# stm32H7_experimenter10.net
KiCad netlist of a schematic drawn in EAGLE
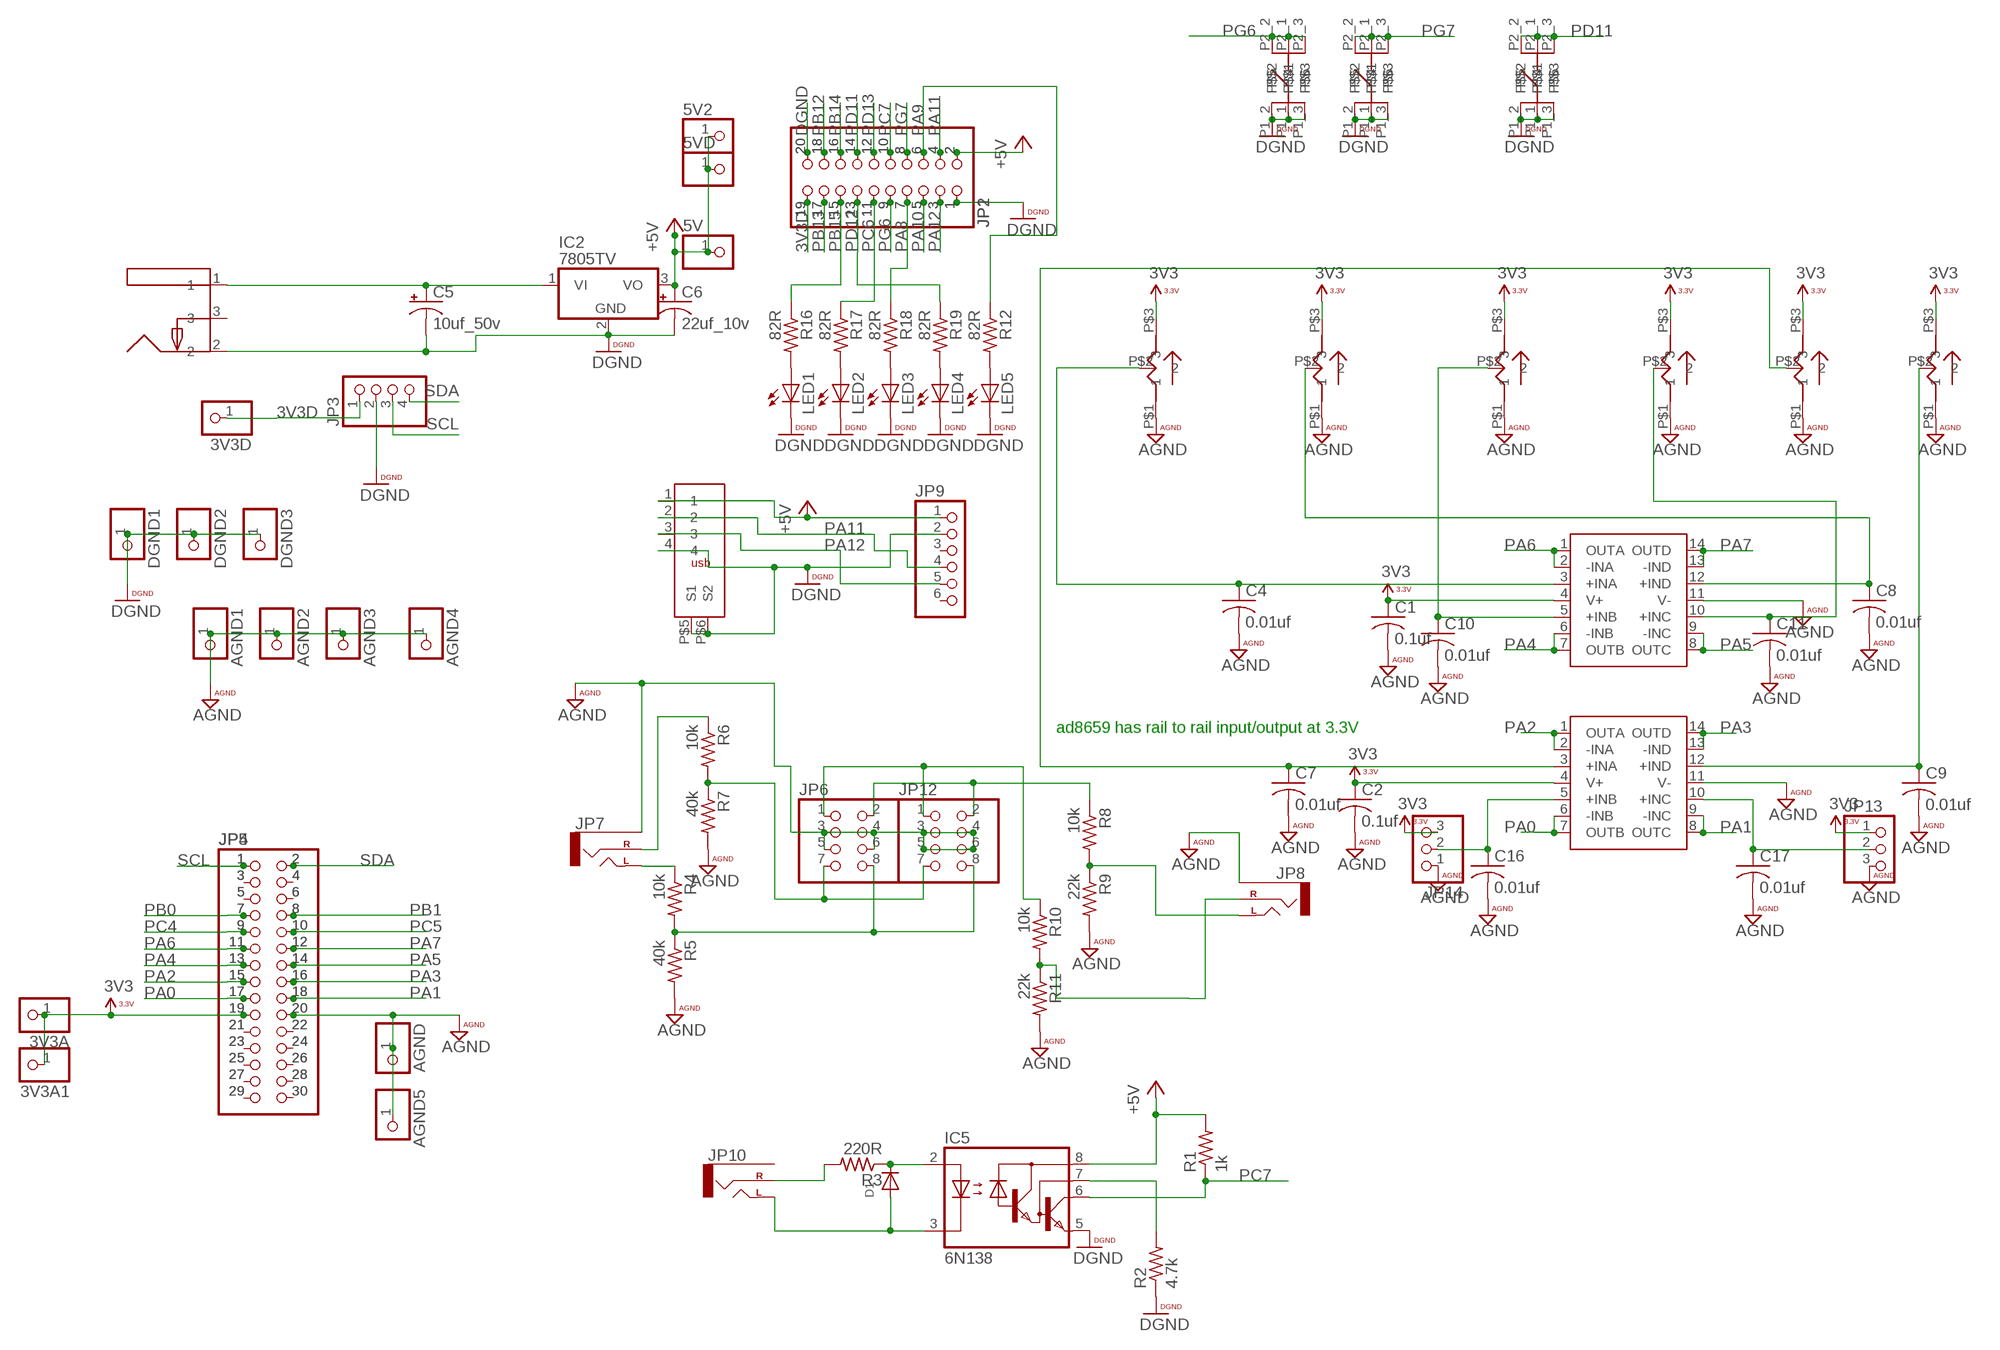
[diagram p0: schematic, sheet 1]

(export (version "E")
  (design (tool "Eeschema 10.0.6"))
  (components
    (comp (ref "3V3A")
      (value "PINHD-1X1")
      (footprint "eagle-import:1X01")
      (fields (field (name "PARTNO") "*DNP"))
      (libsource (lib "eagle-import") (part "PINHD-1X1"))
    )
    (comp (ref "3V3A1")
      (value "PINHD-1X1")
      (footprint "eagle-import:1X01")
      (fields (field (name "PARTNO") "*DNP"))
      (libsource (lib "eagle-import") (part "PINHD-1X1"))
    )
    (comp (ref "3V3D")
      (value "PINHD-1X1")
      (footprint "eagle-import:1X01")
      (fields (field (name "PARTNO") "*DNP"))
      (libsource (lib "eagle-import") (part "PINHD-1X1"))
    )
    (comp (ref "5V")
      (value "PINHD-1X1")
      (footprint "eagle-import:1X01")
      (fields (field (name "PARTNO") "*DNP"))
      (libsource (lib "eagle-import") (part "PINHD-1X1"))
    )
    (comp (ref "5V2")
      (value "PINHD-1X1")
      (footprint "eagle-import:1X01")
      (fields (field (name "PARTNO") "*DNP"))
      (libsource (lib "eagle-import") (part "PINHD-1X1"))
    )
    (comp (ref "5VD")
      (value "PINHD-1X1")
      (footprint "eagle-import:1X01")
      (fields (field (name "PARTNO") "*DNP"))
      (libsource (lib "eagle-import") (part "PINHD-1X1"))
    )
    (comp (ref "AGND")
      (value "PINHD-1X1")
      (footprint "eagle-import:1X01")
      (fields (field (name "PARTNO") "*DNP"))
      (libsource (lib "eagle-import") (part "PINHD-1X1"))
    )
    (comp (ref "AGND1")
      (value "PINHD-1X1")
      (footprint "eagle-import:1X01")
      (fields (field (name "PARTNO") "*DNP"))
      (libsource (lib "eagle-import") (part "PINHD-1X1"))
    )
    (comp (ref "AGND2")
      (value "PINHD-1X1")
      (footprint "eagle-import:1X01")
      (fields (field (name "PARTNO") "*DNP"))
      (libsource (lib "eagle-import") (part "PINHD-1X1"))
    )
    (comp (ref "AGND3")
      (value "PINHD-1X1")
      (footprint "eagle-import:1X01")
      (fields (field (name "PARTNO") "*DNP"))
      (libsource (lib "eagle-import") (part "PINHD-1X1"))
    )
    (comp (ref "AGND4")
      (value "PINHD-1X1")
      (footprint "eagle-import:1X01")
      (fields (field (name "PARTNO") "*DNP"))
      (libsource (lib "eagle-import") (part "PINHD-1X1"))
    )
    (comp (ref "AGND5")
      (value "PINHD-1X1")
      (footprint "eagle-import:1X01")
      (fields (field (name "PARTNO") "*DNP"))
      (libsource (lib "eagle-import") (part "PINHD-1X1"))
    )
    (comp (ref "C1")
      (value "0.1uf")
      (footprint "eagle-import:C025-030X050")
      (fields (field (name "PARTNO") "K104K15X7RF5TL2"))
      (libsource (lib "eagle-import") (part "C-US025-030X050"))
    )
    (comp (ref "C2")
      (value "0.1uf")
      (footprint "eagle-import:C025-030X050")
      (fields (field (name "PARTNO") "K104K15X7RF5TL2"))
      (libsource (lib "eagle-import") (part "C-US025-030X050"))
    )
    (comp (ref "C4")
      (value "0.01uf")
      (footprint "eagle-import:C025-030X050")
      (fields (field (name "PARTNO") "K103K15X7RF5TL2"))
      (libsource (lib "eagle-import") (part "C-US025-030X050"))
    )
    (comp (ref "C5")
      (value "10uf_50v")
      (footprint "eagle-import:SMC_C")
      (fields (field (name "PARTNO") "293D106X9035C2TE3"))
      (libsource (lib "eagle-import") (part "CPOL-USSMCC"))
    )
    (comp (ref "C6")
      (value "22uf_10v")
      (footprint "eagle-import:SMC_C")
      (fields (field (name "PARTNO") "T491C226K016AT"))
      (libsource (lib "eagle-import") (part "CPOL-USSMCC"))
    )
    (comp (ref "C7")
      (value "0.01uf")
      (footprint "eagle-import:C025-030X050")
      (fields (field (name "PARTNO") "K103K15X7RF5TL2"))
      (libsource (lib "eagle-import") (part "C-US025-030X050"))
    )
    (comp (ref "C8")
      (value "0.01uf")
      (footprint "eagle-import:C025-030X050")
      (fields (field (name "PARTNO") "K103K15X7RF5TL2"))
      (libsource (lib "eagle-import") (part "C-US025-030X050"))
    )
    (comp (ref "C9")
      (value "0.01uf")
      (footprint "eagle-import:C025-030X050")
      (fields (field (name "PARTNO") "K103K15X7RF5TL2"))
      (libsource (lib "eagle-import") (part "C-US025-030X050"))
    )
    (comp (ref "C10")
      (value "0.01uf")
      (footprint "eagle-import:C025-030X050")
      (fields (field (name "PARTNO") "K103K15X7RF5TL2"))
      (libsource (lib "eagle-import") (part "C-US025-030X050"))
    )
    (comp (ref "C11")
      (value "0.01uf")
      (footprint "eagle-import:C025-030X050")
      (fields (field (name "PARTNO") "K103K15X7RF5TL2"))
      (libsource (lib "eagle-import") (part "C-US025-030X050"))
    )
    (comp (ref "C16")
      (value "0.01uf")
      (footprint "eagle-import:C025-030X050")
      (fields (field (name "PARTNO") "K103K15X7RF5TL2"))
      (libsource (lib "eagle-import") (part "C-US025-030X050"))
    )
    (comp (ref "C17")
      (value "0.01uf")
      (footprint "eagle-import:C025-030X050")
      (fields (field (name "PARTNO") "K103K15X7RF5TL2"))
      (libsource (lib "eagle-import") (part "C-US025-030X050"))
    )
    (comp (ref "D1")
      (value "DIODEDO-1N4148")
      (footprint "eagle-import:DO-1N4148")
      (fields (field (name "PARTNO") "1N4148"))
      (libsource (lib "eagle-import") (part "DIODEDO-1N4148"))
    )
    (comp (ref "DGND1")
      (value "PINHD-1X1")
      (footprint "eagle-import:1X01")
      (fields (field (name "PARTNO") "*DNP"))
      (libsource (lib "eagle-import") (part "PINHD-1X1"))
    )
    (comp (ref "DGND2")
      (value "PINHD-1X1")
      (footprint "eagle-import:1X01")
      (fields (field (name "PARTNO") "*DNP"))
      (libsource (lib "eagle-import") (part "PINHD-1X1"))
    )
    (comp (ref "DGND3")
      (value "PINHD-1X1")
      (footprint "eagle-import:1X01")
      (fields (field (name "PARTNO") "*DNP"))
      (libsource (lib "eagle-import") (part "PINHD-1X1"))
    )
    (comp (ref "IC1")
      (value "AD8659")
      (footprint "eagle-import:SO14")
      (fields (field (name "PARTNO") "AD8659ARZ-R7"))
      (libsource (lib "eagle-import") (part "AD8659"))
    )
    (comp (ref "IC2")
      (value "7805TV")
      (footprint "eagle-import:TO220V")
      (fields (field (name "PARTNO") "VX7805-1000"))
      (libsource (lib "eagle-import") (part "78TV05"))
    )
    (comp (ref "IC3")
      (value "AD8659")
      (footprint "eagle-import:SO14")
      (fields (field (name "PARTNO") "AD8659ARZ-R7"))
      (libsource (lib "eagle-import") (part "AD8659"))
    )
    (comp (ref "IC5")
      (value "6N138")
      (footprint "eagle-import:DIL08")
      (fields (field (name "MF") "VISHAY/TELEFUNKEN"))
      (libsource (lib "eagle-import") (part "6N138"))
    )
    (comp (ref "JP1")
      (value "PINHD-2X10")
      (footprint "eagle-import:2X10")
      (fields (field (name "PARTNO") "*DNP"))
      (libsource (lib "eagle-import") (part "PINHD-2X10"))
    )
    (comp (ref "JP2")
      (value "PINHD-2X10")
      (footprint "eagle-import:2X10")
      (fields (field (name "PARTNO") "67996-120HLF"))
      (libsource (lib "eagle-import") (part "PINHD-2X10"))
    )
    (comp (ref "JP3")
      (value "PINHD-1X4")
      (footprint "eagle-import:1X04")
      (fields (field (name "PARTNO") "*DNP"))
      (libsource (lib "eagle-import") (part "PINHD-1X4"))
    )
    (comp (ref "JP4")
      (value "PINHD-2X15")
      (footprint "eagle-import:2X15")
      (fields (field (name "PARTNO") "67996-130HLF"))
      (libsource (lib "eagle-import") (part "PINHD-2X15"))
    )
    (comp (ref "JP5")
      (value "PINHD-2X15")
      (footprint "eagle-import:2X15")
      (fields (field (name "PARTNO") "*DNP"))
      (libsource (lib "eagle-import") (part "PINHD-2X15"))
    )
    (comp (ref "JP6")
      (value "PINHD-2X4")
      (footprint "eagle-import:2X04")
      (fields (field (name "PARTNO") "67996-108HLF"))
      (libsource (lib "eagle-import") (part "PINHD-2X4"))
    )
    (comp (ref "JP7")
      (value "AUDIO-JACKPTH")
      (footprint "eagle-import:AUDIO-JACK")
      (fields (field (name "PARTNO") "SJ1-3525N"))
      (libsource (lib "eagle-import") (part "AUDIO-JACKPTH"))
    )
    (comp (ref "JP8")
      (value "AUDIO-JACKPTH")
      (footprint "eagle-import:AUDIO-JACK")
      (fields (field (name "PARTNO") "SJ1-3525N"))
      (libsource (lib "eagle-import") (part "AUDIO-JACKPTH"))
    )
    (comp (ref "JP9")
      (value "PINHD-1X6")
      (footprint "eagle-import:1X06")
      (libsource (lib "eagle-import") (part "PINHD-1X6"))
    )
    (comp (ref "JP10")
      (value "AUDIO-JACKPTH")
      (footprint "eagle-import:AUDIO-JACK")
      (fields (field (name "PARTNO") "SJ1-3525N"))
      (libsource (lib "eagle-import") (part "AUDIO-JACKPTH"))
    )
    (comp (ref "JP12")
      (value "PINHD-2X4")
      (footprint "eagle-import:2X04")
      (fields (field (name "PARTNO") "*DNP"))
      (libsource (lib "eagle-import") (part "PINHD-2X4"))
    )
    (comp (ref "JP13")
      (value "PINHD-1X3")
      (footprint "eagle-import:1X03")
      (fields (field (name "PARTNO") "*DNP"))
      (libsource (lib "eagle-import") (part "PINHD-1X3"))
    )
    (comp (ref "JP14")
      (value "PINHD-1X3")
      (footprint "eagle-import:1X03")
      (fields (field (name "PARTNO") "*DNP"))
      (libsource (lib "eagle-import") (part "PINHD-1X3"))
    )
    (comp (ref "LED1")
      (value "LED3MM")
      (footprint "eagle-import:LED3MM")
      (fields (field (name "PARTNO") "151031SS04000"))
      (libsource (lib "eagle-import") (part "LED3MM"))
    )
    (comp (ref "LED2")
      (value "LED3MM")
      (footprint "eagle-import:LED3MM")
      (fields (field (name "PARTNO") "151031SS04000"))
      (libsource (lib "eagle-import") (part "LED3MM"))
    )
    (comp (ref "LED3")
      (value "LED3MM")
      (footprint "eagle-import:LED3MM")
      (fields (field (name "PARTNO") "151031SS04000"))
      (libsource (lib "eagle-import") (part "LED3MM"))
    )
    (comp (ref "LED4")
      (value "LED3MM")
      (footprint "eagle-import:LED3MM")
      (fields (field (name "PARTNO") "151031SS04000"))
      (libsource (lib "eagle-import") (part "LED3MM"))
    )
    (comp (ref "LED5")
      (value "LED3MM")
      (footprint "eagle-import:LED3MM")
      (fields (field (name "PARTNO") "151031SS04000"))
      (libsource (lib "eagle-import") (part "LED3MM"))
    )
    (comp (ref "P1")
      (value "RK09SONGHUEI")
      (footprint "eagle-import:R0904N")
      (libsource (lib "eagle-import") (part "RK09SONGHUEI"))
    )
    (comp (ref "P2")
      (value "RK09SONGHUEI")
      (footprint "eagle-import:R0904N")
      (libsource (lib "eagle-import") (part "RK09SONGHUEI"))
    )
    (comp (ref "P3")
      (value "RK09SONGHUEI")
      (footprint "eagle-import:R0904N")
      (libsource (lib "eagle-import") (part "RK09SONGHUEI"))
    )
    (comp (ref "P4")
      (value "RK09SONGHUEI")
      (footprint "eagle-import:R0904N")
      (libsource (lib "eagle-import") (part "RK09SONGHUEI"))
    )
    (comp (ref "P5")
      (value "RK09SONGHUEI")
      (footprint "eagle-import:R0904N")
      (libsource (lib "eagle-import") (part "RK09SONGHUEI"))
    )
    (comp (ref "P6")
      (value "RK09SONGHUEI")
      (footprint "eagle-import:R0904N")
      (libsource (lib "eagle-import") (part "RK09SONGHUEI"))
    )
    (comp (ref "R1")
      (value "1k")
      (footprint "eagle-import:0204_5")
      (fields (field (name "PARTNO") "RNMF14FTC1K00"))
      (libsource (lib "eagle-import") (part "R-US_0204/5"))
    )
    (comp (ref "R2")
      (value "4.7k")
      (footprint "eagle-import:0204_5")
      (fields (field (name "PARTNO") "RNMF14FTC4K70"))
      (libsource (lib "eagle-import") (part "R-US_0204/5"))
    )
    (comp (ref "R3")
      (value "220R")
      (footprint "eagle-import:0204_5")
      (fields (field (name "PARTNO") "RNMF14FTC220R"))
      (libsource (lib "eagle-import") (part "R-US_0204/5"))
    )
    (comp (ref "R4")
      (value "10k")
      (footprint "eagle-import:0204_5")
      (fields (field (name "PARTNO") "RNMF14FTC10K0"))
      (libsource (lib "eagle-import") (part "R-US_0204/5"))
    )
    (comp (ref "R5")
      (value "40k")
      (footprint "eagle-import:0204_5")
      (fields (field (name "PARTNO") "RNMF14FTC39K0"))
      (libsource (lib "eagle-import") (part "R-US_0204/5"))
    )
    (comp (ref "R6")
      (value "10k")
      (footprint "eagle-import:0204_5")
      (fields (field (name "PARTNO") "RNMF14FTC10K0"))
      (libsource (lib "eagle-import") (part "R-US_0204/5"))
    )
    (comp (ref "R7")
      (value "40k")
      (footprint "eagle-import:0204_5")
      (fields (field (name "PARTNO") "RNMF14FTC39K0"))
      (libsource (lib "eagle-import") (part "R-US_0204/5"))
    )
    (comp (ref "R8")
      (value "10k")
      (footprint "eagle-import:0204_5")
      (fields (field (name "PARTNO") "RNMF14FTC10K0"))
      (libsource (lib "eagle-import") (part "R-US_0204/5"))
    )
    (comp (ref "R9")
      (value "22k")
      (footprint "eagle-import:0204_5")
      (fields (field (name "PARTNO") "RNMF14FTC22K0"))
      (libsource (lib "eagle-import") (part "R-US_0204/5"))
    )
    (comp (ref "R10")
      (value "10k")
      (footprint "eagle-import:0204_5")
      (fields (field (name "PARTNO") "RNMF14FTC10K0"))
      (libsource (lib "eagle-import") (part "R-US_0204/5"))
    )
    (comp (ref "R11")
      (value "22k")
      (footprint "eagle-import:0204_5")
      (fields (field (name "PARTNO") "RNMF14FTC22K0"))
      (libsource (lib "eagle-import") (part "R-US_0204/5"))
    )
    (comp (ref "R12")
      (value "82R")
      (footprint "eagle-import:0204_5")
      (fields (field (name "PARTNO") "RNMF14FTC82R0"))
      (libsource (lib "eagle-import") (part "R-US_0204/5"))
    )
    (comp (ref "R16")
      (value "82R")
      (footprint "eagle-import:0204V")
      (fields (field (name "PARTNO") "RNMF14FTC82R0"))
      (libsource (lib "eagle-import") (part "R-US_0204/2V"))
    )
    (comp (ref "R17")
      (value "82R")
      (footprint "eagle-import:0204V")
      (fields (field (name "PARTNO") "RNMF14FTC82R0"))
      (libsource (lib "eagle-import") (part "R-US_0204/2V"))
    )
    (comp (ref "R18")
      (value "82R")
      (footprint "eagle-import:0204_5")
      (fields (field (name "PARTNO") "RNMF14FTC82R0"))
      (libsource (lib "eagle-import") (part "R-US_0204/5"))
    )
    (comp (ref "R19")
      (value "82R")
      (footprint "eagle-import:0204_5")
      (fields (field (name "PARTNO") "RNMF14FTC82R0"))
      (libsource (lib "eagle-import") (part "R-US_0204/5"))
    )
    (comp (ref "S1")
      (value "TL52_PLUS")
      (footprint "eagle-import:TL52_PLUS")
      (fields (field (name "PARTNO") "TL52AF160Q"))
      (libsource (lib "eagle-import") (part "TL52_PLUS"))
    )
    (comp (ref "S2")
      (value "TL52_PLUS")
      (footprint "eagle-import:TL52_PLUS")
      (fields (field (name "PARTNO") "TL52AF160Q"))
      (libsource (lib "eagle-import") (part "TL52_PLUS"))
    )
    (comp (ref "S3")
      (value "TL52_PLUS")
      (footprint "eagle-import:TL52_PLUS")
      (fields (field (name "PARTNO") "TL52AF160Q"))
      (libsource (lib "eagle-import") (part "TL52_PLUS"))
    )
    (comp (ref "U$1")
      (value "PJ-058AH_PWR_JACK")
      (footprint "eagle-import:PJ-058AH")
      (libsource (lib "eagle-import") (part "PJ-058AH_PWR_JACK"))
    )
    (comp (ref "U$3")
      (value "USB_292303-1")
      (footprint "eagle-import:292303")
      (libsource (lib "eagle-import") (part "USB_292303-1"))
    )
  )
  (nets
    (net (code "1") (name "+5V") (class "Default")
      (node (ref "5V") (pin "1") (pinfunction "1_1") (pintype "passive"))
      (node (ref "5V2") (pin "1") (pinfunction "1_1") (pintype "passive"))
      (node (ref "5VD") (pin "1") (pinfunction "1_1") (pintype "passive"))
      (node (ref "C6") (pin "+") (pinfunction "+_+") (pintype "passive"))
      (node (ref "IC2") (pin "3") (pinfunction "VO_3") (pintype "passive"))
      (node (ref "IC5") (pin "8") (pinfunction "VCC_8") (pintype "passive"))
      (node (ref "JP1") (pin "2") (pinfunction "2_2") (pintype "passive"))
      (node (ref "JP2") (pin "2") (pinfunction "2_2") (pintype "passive"))
      (node (ref "JP9") (pin "1") (pinfunction "1_1") (pintype "passive"))
      (node (ref "R1") (pin "2") (pinfunction "2_2") (pintype "passive"))
      (node (ref "U$3") (pin "1") (pinfunction "1_1") (pintype "bidirectional"))
    )
    (net (code "2") (name "/3V3D") (class "Default")
      (node (ref "3V3D") (pin "1") (pinfunction "1_1") (pintype "passive"))
      (node (ref "JP1") (pin "19") (pinfunction "19_19") (pintype "passive"))
      (node (ref "JP2") (pin "19") (pinfunction "19_19") (pintype "passive"))
      (node (ref "JP3") (pin "1") (pinfunction "1_1") (pintype "passive"))
    )
    (net (code "3") (name "/PA0") (class "Default")
      (node (ref "IC3") (pin "6") (pinfunction "-INB_6") (pintype "bidirectional"))
      (node (ref "IC3") (pin "7") (pinfunction "OUTB_7") (pintype "bidirectional"))
      (node (ref "JP4") (pin "17") (pinfunction "17_17") (pintype "passive"))
      (node (ref "JP5") (pin "17") (pinfunction "17_17") (pintype "passive"))
    )
    (net (code "4") (name "/PA1") (class "Default")
      (node (ref "IC3") (pin "8") (pinfunction "OUTC_8") (pintype "bidirectional"))
      (node (ref "IC3") (pin "9") (pinfunction "-INC_9") (pintype "bidirectional"))
      (node (ref "JP4") (pin "18") (pinfunction "18_18") (pintype "passive"))
      (node (ref "JP5") (pin "18") (pinfunction "18_18") (pintype "passive"))
    )
    (net (code "5") (name "/PA2") (class "Default")
      (node (ref "IC3") (pin "1") (pinfunction "OUTA_1") (pintype "bidirectional"))
      (node (ref "IC3") (pin "2") (pinfunction "-INA_2") (pintype "bidirectional"))
      (node (ref "JP4") (pin "15") (pinfunction "15_15") (pintype "passive"))
      (node (ref "JP5") (pin "15") (pinfunction "15_15") (pintype "passive"))
    )
    (net (code "6") (name "/PA3") (class "Default")
      (node (ref "IC3") (pin "13") (pinfunction "-IND_13") (pintype "bidirectional"))
      (node (ref "IC3") (pin "14") (pinfunction "OUTD_14") (pintype "bidirectional"))
      (node (ref "JP4") (pin "16") (pinfunction "16_16") (pintype "passive"))
      (node (ref "JP5") (pin "16") (pinfunction "16_16") (pintype "passive"))
    )
    (net (code "7") (name "/PA4") (class "Default")
      (node (ref "IC1") (pin "6") (pinfunction "-INB_6") (pintype "bidirectional"))
      (node (ref "IC1") (pin "7") (pinfunction "OUTB_7") (pintype "bidirectional"))
      (node (ref "JP4") (pin "13") (pinfunction "13_13") (pintype "passive"))
      (node (ref "JP5") (pin "13") (pinfunction "13_13") (pintype "passive"))
    )
    (net (code "8") (name "/PA5") (class "Default")
      (node (ref "IC1") (pin "8") (pinfunction "OUTC_8") (pintype "bidirectional"))
      (node (ref "IC1") (pin "9") (pinfunction "-INC_9") (pintype "bidirectional"))
      (node (ref "JP4") (pin "14") (pinfunction "14_14") (pintype "passive"))
      (node (ref "JP5") (pin "14") (pinfunction "14_14") (pintype "passive"))
    )
    (net (code "9") (name "/PA6") (class "Default")
      (node (ref "IC1") (pin "1") (pinfunction "OUTA_1") (pintype "bidirectional"))
      (node (ref "IC1") (pin "2") (pinfunction "-INA_2") (pintype "bidirectional"))
      (node (ref "JP4") (pin "11") (pinfunction "11_11") (pintype "passive"))
      (node (ref "JP5") (pin "11") (pinfunction "11_11") (pintype "passive"))
    )
    (net (code "10") (name "/PA7") (class "Default")
      (node (ref "IC1") (pin "13") (pinfunction "-IND_13") (pintype "bidirectional"))
      (node (ref "IC1") (pin "14") (pinfunction "OUTD_14") (pintype "bidirectional"))
      (node (ref "JP4") (pin "12") (pinfunction "12_12") (pintype "passive"))
      (node (ref "JP5") (pin "12") (pinfunction "12_12") (pintype "passive"))
    )
    (net (code "11") (name "/PA8") (class "Default")
      (node (ref "JP1") (pin "7") (pinfunction "7_7") (pintype "passive"))
      (node (ref "JP2") (pin "7") (pinfunction "7_7") (pintype "passive"))
      (node (ref "R18") (pin "1") (pinfunction "1_1") (pintype "passive"))
    )
    (net (code "12") (name "/PA9") (class "Default")
      (node (ref "JP1") (pin "6") (pinfunction "6_6") (pintype "passive"))
      (node (ref "JP2") (pin "6") (pinfunction "6_6") (pintype "passive"))
      (node (ref "R12") (pin "1") (pinfunction "1_1") (pintype "passive"))
    )
    (net (code "13") (name "/PA10") (class "Default")
      (node (ref "JP1") (pin "5") (pinfunction "5_5") (pintype "passive"))
      (node (ref "JP2") (pin "5") (pinfunction "5_5") (pintype "passive"))
    )
    (net (code "14") (name "/PA11") (class "Default")
      (node (ref "JP1") (pin "4") (pinfunction "4_4") (pintype "passive"))
      (node (ref "JP2") (pin "4") (pinfunction "4_4") (pintype "passive"))
      (node (ref "JP9") (pin "4") (pinfunction "4_4") (pintype "passive"))
      (node (ref "U$3") (pin "2") (pinfunction "2_2") (pintype "bidirectional"))
    )
    (net (code "15") (name "/PA12") (class "Default")
      (node (ref "JP1") (pin "3") (pinfunction "3_3") (pintype "passive"))
      (node (ref "JP2") (pin "3") (pinfunction "3_3") (pintype "passive"))
      (node (ref "JP9") (pin "5") (pinfunction "5_5") (pintype "passive"))
      (node (ref "U$3") (pin "3") (pinfunction "3_3") (pintype "bidirectional"))
    )
    (net (code "16") (name "/PB0") (class "Default")
      (node (ref "JP4") (pin "7") (pinfunction "7_7") (pintype "passive"))
      (node (ref "JP5") (pin "7") (pinfunction "7_7") (pintype "passive"))
    )
    (net (code "17") (name "/PB1") (class "Default")
      (node (ref "JP4") (pin "8") (pinfunction "8_8") (pintype "passive"))
      (node (ref "JP5") (pin "8") (pinfunction "8_8") (pintype "passive"))
    )
    (net (code "18") (name "/PB12") (class "Default")
      (node (ref "JP1") (pin "18") (pinfunction "18_18") (pintype "passive"))
      (node (ref "JP2") (pin "18") (pinfunction "18_18") (pintype "passive"))
    )
    (net (code "19") (name "/PB13") (class "Default")
      (node (ref "JP1") (pin "17") (pinfunction "17_17") (pintype "passive"))
      (node (ref "JP2") (pin "17") (pinfunction "17_17") (pintype "passive"))
    )
    (net (code "20") (name "/PB14") (class "Default")
      (node (ref "JP1") (pin "16") (pinfunction "16_16") (pintype "passive"))
      (node (ref "JP2") (pin "16") (pinfunction "16_16") (pintype "passive"))
    )
    (net (code "21") (name "/PB15") (class "Default")
      (node (ref "JP1") (pin "15") (pinfunction "15_15") (pintype "passive"))
      (node (ref "JP2") (pin "15") (pinfunction "15_15") (pintype "passive"))
      (node (ref "R16") (pin "1") (pinfunction "1_1") (pintype "passive"))
    )
    (net (code "22") (name "/PC4") (class "Default")
      (node (ref "JP4") (pin "9") (pinfunction "9_9") (pintype "passive"))
      (node (ref "JP5") (pin "9") (pinfunction "9_9") (pintype "passive"))
    )
    (net (code "23") (name "/PC5") (class "Default")
      (node (ref "JP4") (pin "10") (pinfunction "10_10") (pintype "passive"))
      (node (ref "JP5") (pin "10") (pinfunction "10_10") (pintype "passive"))
    )
    (net (code "24") (name "/PC6") (class "Default")
      (node (ref "JP1") (pin "11") (pinfunction "11_11") (pintype "passive"))
      (node (ref "JP2") (pin "11") (pinfunction "11_11") (pintype "passive"))
      (node (ref "R17") (pin "1") (pinfunction "1_1") (pintype "passive"))
    )
    (net (code "25") (name "/PC7") (class "Default")
      (node (ref "IC5") (pin "6") (pinfunction "VO_6") (pintype "passive"))
      (node (ref "JP1") (pin "10") (pinfunction "10_10") (pintype "passive"))
      (node (ref "JP2") (pin "10") (pinfunction "10_10") (pintype "passive"))
      (node (ref "R1") (pin "1") (pinfunction "1_1") (pintype "passive"))
    )
    (net (code "26") (name "/PD11") (class "Default")
      (node (ref "JP1") (pin "14") (pinfunction "14_14") (pintype "passive"))
      (node (ref "JP2") (pin "14") (pinfunction "14_14") (pintype "passive"))
      (node (ref "S3") (pin "P2_1") (pinfunction "P$4_P2_1") (pintype "bidirectional"))
      (node (ref "S3") (pin "P2_2") (pinfunction "P$5_P2_2") (pintype "bidirectional"))
      (node (ref "S3") (pin "P2_3") (pinfunction "P$6_P2_3") (pintype "bidirectional"))
    )
    (net (code "27") (name "/PD12") (class "Default")
      (node (ref "JP1") (pin "13") (pinfunction "13_13") (pintype "passive"))
      (node (ref "JP2") (pin "13") (pinfunction "13_13") (pintype "passive"))
      (node (ref "R19") (pin "1") (pinfunction "1_1") (pintype "passive"))
    )
    (net (code "28") (name "/PD13") (class "Default")
      (node (ref "JP1") (pin "12") (pinfunction "12_12") (pintype "passive"))
      (node (ref "JP2") (pin "12") (pinfunction "12_12") (pintype "passive"))
    )
    (net (code "29") (name "/PG6") (class "Default")
      (node (ref "JP1") (pin "9") (pinfunction "9_9") (pintype "passive"))
      (node (ref "JP2") (pin "9") (pinfunction "9_9") (pintype "passive"))
      (node (ref "S1") (pin "P2_1") (pinfunction "P$4_P2_1") (pintype "bidirectional"))
      (node (ref "S1") (pin "P2_2") (pinfunction "P$5_P2_2") (pintype "bidirectional"))
      (node (ref "S1") (pin "P2_3") (pinfunction "P$6_P2_3") (pintype "bidirectional"))
    )
    (net (code "30") (name "/PG7") (class "Default")
      (node (ref "JP1") (pin "8") (pinfunction "8_8") (pintype "passive"))
      (node (ref "JP2") (pin "8") (pinfunction "8_8") (pintype "passive"))
      (node (ref "S2") (pin "P2_1") (pinfunction "P$4_P2_1") (pintype "bidirectional"))
      (node (ref "S2") (pin "P2_2") (pinfunction "P$5_P2_2") (pintype "bidirectional"))
      (node (ref "S2") (pin "P2_3") (pinfunction "P$6_P2_3") (pintype "bidirectional"))
    )
    (net (code "31") (name "/SCL") (class "Default")
      (node (ref "JP3") (pin "3") (pinfunction "3_3") (pintype "passive"))
      (node (ref "JP4") (pin "1") (pinfunction "1_1") (pintype "passive"))
      (node (ref "JP5") (pin "1") (pinfunction "1_1") (pintype "passive"))
    )
    (net (code "32") (name "/SDA") (class "Default")
      (node (ref "JP3") (pin "4") (pinfunction "4_4") (pintype "passive"))
      (node (ref "JP4") (pin "2") (pinfunction "2_2") (pintype "passive"))
      (node (ref "JP5") (pin "2") (pinfunction "2_2") (pintype "passive"))
    )
    (net (code "33") (name "3V3") (class "Default")
      (node (ref "3V3A") (pin "1") (pinfunction "1_1") (pintype "passive"))
      (node (ref "3V3A1") (pin "1") (pinfunction "1_1") (pintype "passive"))
      (node (ref "C1") (pin "1") (pinfunction "1_1") (pintype "passive"))
      (node (ref "C2") (pin "1") (pinfunction "1_1") (pintype "passive"))
      (node (ref "IC1") (pin "4") (pinfunction "V+_4") (pintype "bidirectional"))
      (node (ref "IC3") (pin "4") (pinfunction "V+_4") (pintype "bidirectional"))
      (node (ref "JP13") (pin "1") (pinfunction "1_1") (pintype "passive"))
      (node (ref "JP14") (pin "3") (pinfunction "3_3") (pintype "passive"))
      (node (ref "JP4") (pin "19") (pinfunction "19_19") (pintype "passive"))
      (node (ref "JP5") (pin "19") (pinfunction "19_19") (pintype "passive"))
      (node (ref "P1") (pin "P$3") (pinfunction "3_P$3") (pintype "bidirectional"))
      (node (ref "P2") (pin "P$3") (pinfunction "3_P$3") (pintype "bidirectional"))
      (node (ref "P3") (pin "P$3") (pinfunction "3_P$3") (pintype "bidirectional"))
      (node (ref "P4") (pin "P$3") (pinfunction "3_P$3") (pintype "bidirectional"))
      (node (ref "P5") (pin "P$3") (pinfunction "3_P$3") (pintype "bidirectional"))
      (node (ref "P6") (pin "P$3") (pinfunction "3_P$3") (pintype "bidirectional"))
    )
    (net (code "34") (name "AGND") (class "Default")
      (node (ref "AGND") (pin "1") (pinfunction "1_1") (pintype "passive"))
      (node (ref "AGND1") (pin "1") (pinfunction "1_1") (pintype "passive"))
      (node (ref "AGND2") (pin "1") (pinfunction "1_1") (pintype "passive"))
      (node (ref "AGND3") (pin "1") (pinfunction "1_1") (pintype "passive"))
      (node (ref "AGND4") (pin "1") (pinfunction "1_1") (pintype "passive"))
      (node (ref "AGND5") (pin "1") (pinfunction "1_1") (pintype "passive"))
      (node (ref "C1") (pin "2") (pinfunction "2_2") (pintype "passive"))
      (node (ref "C10") (pin "2") (pinfunction "2_2") (pintype "passive"))
      (node (ref "C11") (pin "2") (pinfunction "2_2") (pintype "passive"))
      (node (ref "C16") (pin "2") (pinfunction "2_2") (pintype "passive"))
      (node (ref "C17") (pin "2") (pinfunction "2_2") (pintype "passive"))
      (node (ref "C2") (pin "2") (pinfunction "2_2") (pintype "passive"))
      (node (ref "C4") (pin "2") (pinfunction "2_2") (pintype "passive"))
      (node (ref "C7") (pin "2") (pinfunction "2_2") (pintype "passive"))
      (node (ref "C8") (pin "2") (pinfunction "2_2") (pintype "passive"))
      (node (ref "C9") (pin "2") (pinfunction "2_2") (pintype "passive"))
      (node (ref "IC1") (pin "11") (pinfunction "V-_11") (pintype "bidirectional"))
      (node (ref "IC3") (pin "11") (pinfunction "V-_11") (pintype "bidirectional"))
      (node (ref "JP12") (pin "3") (pinfunction "3_3") (pintype "passive"))
      (node (ref "JP12") (pin "4") (pinfunction "4_4") (pintype "passive"))
      (node (ref "JP12") (pin "5") (pinfunction "5_5") (pintype "passive"))
      (node (ref "JP12") (pin "6") (pinfunction "6_6") (pintype "passive"))
      (node (ref "JP13") (pin "3") (pinfunction "3_3") (pintype "passive"))
      (node (ref "JP14") (pin "1") (pinfunction "1_1") (pintype "passive"))
      (node (ref "JP4") (pin "20") (pinfunction "20_20") (pintype "passive"))
      (node (ref "JP5") (pin "20") (pinfunction "20_20") (pintype "passive"))
      (node (ref "JP6") (pin "3") (pinfunction "3_3") (pintype "passive"))
      (node (ref "JP6") (pin "4") (pinfunction "4_4") (pintype "passive"))
      (node (ref "JP6") (pin "5") (pinfunction "5_5") (pintype "passive"))
      (node (ref "JP6") (pin "6") (pinfunction "6_6") (pintype "passive"))
      (node (ref "JP7") (pin "SLEEVE") (pinfunction "SLEEVE_SLEEVE") (pintype "bidirectional"))
      (node (ref "JP8") (pin "SLEEVE") (pinfunction "SLEEVE_SLEEVE") (pintype "bidirectional"))
      (node (ref "P1") (pin "P$1") (pinfunction "1_P$1") (pintype "bidirectional"))
      (node (ref "P2") (pin "P$1") (pinfunction "1_P$1") (pintype "bidirectional"))
      (node (ref "P3") (pin "P$1") (pinfunction "1_P$1") (pintype "bidirectional"))
      (node (ref "P4") (pin "P$1") (pinfunction "1_P$1") (pintype "bidirectional"))
      (node (ref "P5") (pin "P$1") (pinfunction "1_P$1") (pintype "bidirectional"))
      (node (ref "P6") (pin "P$1") (pinfunction "1_P$1") (pintype "bidirectional"))
      (node (ref "R11") (pin "2") (pinfunction "2_2") (pintype "passive"))
      (node (ref "R5") (pin "2") (pinfunction "2_2") (pintype "passive"))
      (node (ref "R7") (pin "2") (pinfunction "2_2") (pintype "passive"))
      (node (ref "R9") (pin "2") (pinfunction "2_2") (pintype "passive"))
    )
    (net (code "35") (name "DGND") (class "Default")
      (node (ref "C5") (pin "-") (pinfunction "-_-") (pintype "passive"))
      (node (ref "C6") (pin "-") (pinfunction "-_-") (pintype "passive"))
      (node (ref "DGND1") (pin "1") (pinfunction "1_1") (pintype "passive"))
      (node (ref "DGND2") (pin "1") (pinfunction "1_1") (pintype "passive"))
      (node (ref "DGND3") (pin "1") (pinfunction "1_1") (pintype "passive"))
      (node (ref "IC2") (pin "2") (pinfunction "GND_2") (pintype "passive"))
      (node (ref "IC5") (pin "5") (pinfunction "GND_5") (pintype "passive"))
      (node (ref "JP1") (pin "1") (pinfunction "1_1") (pintype "passive"))
      (node (ref "JP1") (pin "20") (pinfunction "20_20") (pintype "passive"))
      (node (ref "JP2") (pin "1") (pinfunction "1_1") (pintype "passive"))
      (node (ref "JP2") (pin "20") (pinfunction "20_20") (pintype "passive"))
      (node (ref "JP3") (pin "2") (pinfunction "2_2") (pintype "passive"))
      (node (ref "JP9") (pin "2") (pinfunction "2_2") (pintype "passive"))
      (node (ref "LED1") (pin "K") (pinfunction "C_K") (pintype "passive"))
      (node (ref "LED2") (pin "K") (pinfunction "C_K") (pintype "passive"))
      (node (ref "LED3") (pin "K") (pinfunction "C_K") (pintype "passive"))
      (node (ref "LED4") (pin "K") (pinfunction "C_K") (pintype "passive"))
      (node (ref "LED5") (pin "K") (pinfunction "C_K") (pintype "passive"))
      (node (ref "R2") (pin "1") (pinfunction "1_1") (pintype "passive"))
      (node (ref "S1") (pin "P1_1") (pinfunction "P$1_P1_1") (pintype "bidirectional"))
      (node (ref "S1") (pin "P1_2") (pinfunction "P$2_P1_2") (pintype "bidirectional"))
      (node (ref "S1") (pin "P1_3") (pinfunction "P$3_P1_3") (pintype "bidirectional"))
      (node (ref "S2") (pin "P1_1") (pinfunction "P$1_P1_1") (pintype "bidirectional"))
      (node (ref "S2") (pin "P1_2") (pinfunction "P$2_P1_2") (pintype "bidirectional"))
      (node (ref "S2") (pin "P1_3") (pinfunction "P$3_P1_3") (pintype "bidirectional"))
      (node (ref "S3") (pin "P1_1") (pinfunction "P$1_P1_1") (pintype "bidirectional"))
      (node (ref "S3") (pin "P1_2") (pinfunction "P$2_P1_2") (pintype "bidirectional"))
      (node (ref "S3") (pin "P1_3") (pinfunction "P$3_P1_3") (pintype "bidirectional"))
      (node (ref "U$1") (pin "2") (pinfunction "2_2") (pintype "bidirectional"))
      (node (ref "U$3") (pin "4") (pinfunction "4_4") (pintype "bidirectional"))
      (node (ref "U$3") (pin "P$5") (pinfunction "S1_P$5") (pintype "bidirectional"))
      (node (ref "U$3") (pin "P$6") (pinfunction "S2_P$6") (pintype "bidirectional"))
    )
    (net (code "36") (name "Net-(IC1-+INA)") (class "Default")
      (node (ref "C4") (pin "1") (pinfunction "1_1") (pintype "passive"))
      (node (ref "IC1") (pin "3") (pinfunction "+INA_3") (pintype "bidirectional"))
      (node (ref "P1") (pin "P$2") (pinfunction "2_P$2") (pintype "bidirectional"))
    )
    (net (code "37") (name "Net-(IC1-+INB)") (class "Default")
      (node (ref "C10") (pin "1") (pinfunction "1_1") (pintype "passive"))
      (node (ref "IC1") (pin "5") (pinfunction "+INB_5") (pintype "bidirectional"))
      (node (ref "P3") (pin "P$2") (pinfunction "2_P$2") (pintype "bidirectional"))
    )
    (net (code "38") (name "Net-(IC1-+INC)") (class "Default")
      (node (ref "C11") (pin "1") (pinfunction "1_1") (pintype "passive"))
      (node (ref "IC1") (pin "10") (pinfunction "+INC_10") (pintype "bidirectional"))
      (node (ref "P4") (pin "P$2") (pinfunction "2_P$2") (pintype "bidirectional"))
    )
    (net (code "39") (name "Net-(IC1-+IND)") (class "Default")
      (node (ref "C8") (pin "1") (pinfunction "1_1") (pintype "passive"))
      (node (ref "IC1") (pin "12") (pinfunction "+IND_12") (pintype "bidirectional"))
      (node (ref "P2") (pin "P$2") (pinfunction "2_P$2") (pintype "bidirectional"))
    )
    (net (code "40") (name "Net-(IC2-VI)") (class "Default")
      (node (ref "C5") (pin "+") (pinfunction "+_+") (pintype "passive"))
      (node (ref "IC2") (pin "1") (pinfunction "VI_1") (pintype "input"))
      (node (ref "U$1") (pin "1") (pinfunction "1_1") (pintype "bidirectional"))
    )
    (net (code "41") (name "Net-(IC3-+INA)") (class "Default")
      (node (ref "C7") (pin "1") (pinfunction "1_1") (pintype "passive"))
      (node (ref "IC3") (pin "3") (pinfunction "+INA_3") (pintype "bidirectional"))
      (node (ref "P5") (pin "P$2") (pinfunction "2_P$2") (pintype "bidirectional"))
    )
    (net (code "42") (name "Net-(IC3-+INB)") (class "Default")
      (node (ref "C16") (pin "1") (pinfunction "1_1") (pintype "passive"))
      (node (ref "IC3") (pin "5") (pinfunction "+INB_5") (pintype "bidirectional"))
      (node (ref "JP14") (pin "2") (pinfunction "2_2") (pintype "passive"))
    )
    (net (code "43") (name "Net-(IC3-+INC)") (class "Default")
      (node (ref "C17") (pin "1") (pinfunction "1_1") (pintype "passive"))
      (node (ref "IC3") (pin "10") (pinfunction "+INC_10") (pintype "bidirectional"))
      (node (ref "JP13") (pin "2") (pinfunction "2_2") (pintype "passive"))
    )
    (net (code "44") (name "Net-(IC3-+IND)") (class "Default")
      (node (ref "C9") (pin "1") (pinfunction "1_1") (pintype "passive"))
      (node (ref "IC3") (pin "12") (pinfunction "+IND_12") (pintype "bidirectional"))
      (node (ref "P6") (pin "P$2") (pinfunction "2_P$2") (pintype "bidirectional"))
    )
    (net (code "45") (name "Net-(IC5-A)") (class "Default")
      (node (ref "D1") (pin "C") (pinfunction "C_C") (pintype "passive"))
      (node (ref "IC5") (pin "2") (pinfunction "A_2") (pintype "passive"))
      (node (ref "R3") (pin "1") (pinfunction "1_1") (pintype "passive"))
    )
    (net (code "46") (name "Net-(IC5-C)") (class "Default")
      (node (ref "D1") (pin "A") (pinfunction "A_A") (pintype "passive"))
      (node (ref "IC5") (pin "3") (pinfunction "C_3") (pintype "passive"))
      (node (ref "JP10") (pin "TIP") (pinfunction "LEFT_TIP") (pintype "bidirectional"))
    )
    (net (code "47") (name "Net-(IC5-VB)") (class "Default")
      (node (ref "IC5") (pin "7") (pinfunction "VB_7") (pintype "passive"))
      (node (ref "R2") (pin "2") (pinfunction "2_2") (pintype "passive"))
    )
    (net (code "48") (name "Net-(JP4-Pad3)") (class "Default")
      (node (ref "JP4") (pin "3") (pinfunction "3_3") (pintype "passive"))
      (node (ref "JP5") (pin "3") (pinfunction "3_3") (pintype "passive"))
    )
    (net (code "49") (name "Net-(JP4-Pad4)") (class "Default")
      (node (ref "JP4") (pin "4") (pinfunction "4_4") (pintype "passive"))
      (node (ref "JP5") (pin "4") (pinfunction "4_4") (pintype "passive"))
    )
    (net (code "50") (name "Net-(JP4-Pad5)") (class "Default")
      (node (ref "JP4") (pin "5") (pinfunction "5_5") (pintype "passive"))
      (node (ref "JP5") (pin "5") (pinfunction "5_5") (pintype "passive"))
    )
    (net (code "51") (name "Net-(JP4-Pad6)") (class "Default")
      (node (ref "JP4") (pin "6") (pinfunction "6_6") (pintype "passive"))
      (node (ref "JP5") (pin "6") (pinfunction "6_6") (pintype "passive"))
    )
    (net (code "52") (name "Net-(JP4-Pad21)") (class "Default")
      (node (ref "JP4") (pin "21") (pinfunction "21_21") (pintype "passive"))
      (node (ref "JP5") (pin "21") (pinfunction "21_21") (pintype "passive"))
    )
    (net (code "53") (name "Net-(JP4-Pad22)") (class "Default")
      (node (ref "JP4") (pin "22") (pinfunction "22_22") (pintype "passive"))
      (node (ref "JP5") (pin "22") (pinfunction "22_22") (pintype "passive"))
    )
    (net (code "54") (name "Net-(JP4-Pad23)") (class "Default")
      (node (ref "JP4") (pin "23") (pinfunction "23_23") (pintype "passive"))
      (node (ref "JP5") (pin "23") (pinfunction "23_23") (pintype "passive"))
    )
    (net (code "55") (name "Net-(JP4-Pad24)") (class "Default")
      (node (ref "JP4") (pin "24") (pinfunction "24_24") (pintype "passive"))
      (node (ref "JP5") (pin "24") (pinfunction "24_24") (pintype "passive"))
    )
    (net (code "56") (name "Net-(JP4-Pad25)") (class "Default")
      (node (ref "JP4") (pin "25") (pinfunction "25_25") (pintype "passive"))
      (node (ref "JP5") (pin "25") (pinfunction "25_25") (pintype "passive"))
    )
    (net (code "57") (name "Net-(JP4-Pad26)") (class "Default")
      (node (ref "JP4") (pin "26") (pinfunction "26_26") (pintype "passive"))
      (node (ref "JP5") (pin "26") (pinfunction "26_26") (pintype "passive"))
    )
    (net (code "58") (name "Net-(JP4-Pad27)") (class "Default")
      (node (ref "JP4") (pin "27") (pinfunction "27_27") (pintype "passive"))
      (node (ref "JP5") (pin "27") (pinfunction "27_27") (pintype "passive"))
    )
    (net (code "59") (name "Net-(JP4-Pad28)") (class "Default")
      (node (ref "JP4") (pin "28") (pinfunction "28_28") (pintype "passive"))
      (node (ref "JP5") (pin "28") (pinfunction "28_28") (pintype "passive"))
    )
    (net (code "60") (name "Net-(JP4-Pad29)") (class "Default")
      (node (ref "JP4") (pin "29") (pinfunction "29_29") (pintype "passive"))
      (node (ref "JP5") (pin "29") (pinfunction "29_29") (pintype "passive"))
    )
    (net (code "61") (name "Net-(JP4-Pad30)") (class "Default")
      (node (ref "JP4") (pin "30") (pinfunction "30_30") (pintype "passive"))
      (node (ref "JP5") (pin "30") (pinfunction "30_30") (pintype "passive"))
    )
    (net (code "62") (name "Net-(JP7-LEFT)") (class "Default")
      (node (ref "JP7") (pin "TIP") (pinfunction "LEFT_TIP") (pintype "bidirectional"))
      (node (ref "R4") (pin "1") (pinfunction "1_1") (pintype "passive"))
    )
    (net (code "63") (name "Net-(JP7-RIGHT)") (class "Default")
      (node (ref "JP7") (pin "RING") (pinfunction "RIGHT_RING") (pintype "bidirectional"))
      (node (ref "R6") (pin "1") (pinfunction "1_1") (pintype "passive"))
    )
    (net (code "64") (name "Net-(JP8-LEFT)") (class "Default")
      (node (ref "JP8") (pin "TIP") (pinfunction "LEFT_TIP") (pintype "bidirectional"))
      (node (ref "R8") (pin "2") (pinfunction "2_2") (pintype "passive"))
      (node (ref "R9") (pin "1") (pinfunction "1_1") (pintype "passive"))
    )
    (net (code "65") (name "Net-(JP8-RIGHT)") (class "Default")
      (node (ref "JP8") (pin "RING") (pinfunction "RIGHT_RING") (pintype "bidirectional"))
      (node (ref "R10") (pin "2") (pinfunction "2_2") (pintype "passive"))
      (node (ref "R11") (pin "1") (pinfunction "1_1") (pintype "passive"))
    )
    (net (code "66") (name "Net-(JP10-RIGHT)") (class "Default")
      (node (ref "JP10") (pin "RING") (pinfunction "RIGHT_RING") (pintype "bidirectional"))
      (node (ref "R3") (pin "2") (pinfunction "2_2") (pintype "passive"))
    )
    (net (code "67") (name "Net-(JP12-Pad1)") (class "Default")
      (node (ref "JP12") (pin "1") (pinfunction "1_1") (pintype "passive"))
      (node (ref "JP6") (pin "1") (pinfunction "1_1") (pintype "passive"))
      (node (ref "R10") (pin "1") (pinfunction "1_1") (pintype "passive"))
    )
    (net (code "68") (name "Net-(JP12-Pad2)") (class "Default")
      (node (ref "JP12") (pin "2") (pinfunction "2_2") (pintype "passive"))
      (node (ref "JP6") (pin "2") (pinfunction "2_2") (pintype "passive"))
      (node (ref "R8") (pin "1") (pinfunction "1_1") (pintype "passive"))
    )
    (net (code "69") (name "Net-(JP12-Pad7)") (class "Default")
      (node (ref "JP12") (pin "7") (pinfunction "7_7") (pintype "passive"))
      (node (ref "JP6") (pin "7") (pinfunction "7_7") (pintype "passive"))
      (node (ref "R6") (pin "2") (pinfunction "2_2") (pintype "passive"))
      (node (ref "R7") (pin "1") (pinfunction "1_1") (pintype "passive"))
    )
    (net (code "70") (name "Net-(JP12-Pad8)") (class "Default")
      (node (ref "JP12") (pin "8") (pinfunction "8_8") (pintype "passive"))
      (node (ref "JP6") (pin "8") (pinfunction "8_8") (pintype "passive"))
      (node (ref "R4") (pin "2") (pinfunction "2_2") (pintype "passive"))
      (node (ref "R5") (pin "1") (pinfunction "1_1") (pintype "passive"))
    )
    (net (code "71") (name "Net-(LED1-PadA)") (class "Default")
      (node (ref "LED1") (pin "A") (pinfunction "A_A") (pintype "passive"))
      (node (ref "R16") (pin "2") (pinfunction "2_2") (pintype "passive"))
    )
    (net (code "72") (name "Net-(LED2-PadA)") (class "Default")
      (node (ref "LED2") (pin "A") (pinfunction "A_A") (pintype "passive"))
      (node (ref "R17") (pin "2") (pinfunction "2_2") (pintype "passive"))
    )
    (net (code "73") (name "Net-(LED3-PadA)") (class "Default")
      (node (ref "LED3") (pin "A") (pinfunction "A_A") (pintype "passive"))
      (node (ref "R18") (pin "2") (pinfunction "2_2") (pintype "passive"))
    )
    (net (code "74") (name "Net-(LED4-PadA)") (class "Default")
      (node (ref "LED4") (pin "A") (pinfunction "A_A") (pintype "passive"))
      (node (ref "R19") (pin "2") (pinfunction "2_2") (pintype "passive"))
    )
    (net (code "75") (name "Net-(LED5-PadA)") (class "Default")
      (node (ref "LED5") (pin "A") (pinfunction "A_A") (pintype "passive"))
      (node (ref "R12") (pin "2") (pinfunction "2_2") (pintype "passive"))
    )
    (net (code "76") (name "unconnected-(JP9-Pad3)") (class "Default")
      (node (ref "JP9") (pin "3") (pinfunction "3_3") (pintype "passive"))
    )
    (net (code "77") (name "unconnected-(JP9-Pad6)") (class "Default")
      (node (ref "JP9") (pin "6") (pinfunction "6_6") (pintype "passive"))
    )
    (net (code "78") (name "unconnected-(JP10-PadSLEEVE)") (class "Default")
      (node (ref "JP10") (pin "SLEEVE") (pinfunction "SLEEVE_SLEEVE") (pintype "bidirectional"))
    )
    (net (code "79") (name "unconnected-(U$1-Pad3)") (class "Default")
      (node (ref "U$1") (pin "3") (pinfunction "3_3") (pintype "bidirectional"))
    )
  )
)
